# RS232Multiplexer.net
KiCad netlist of a schematic drawn in EAGLE
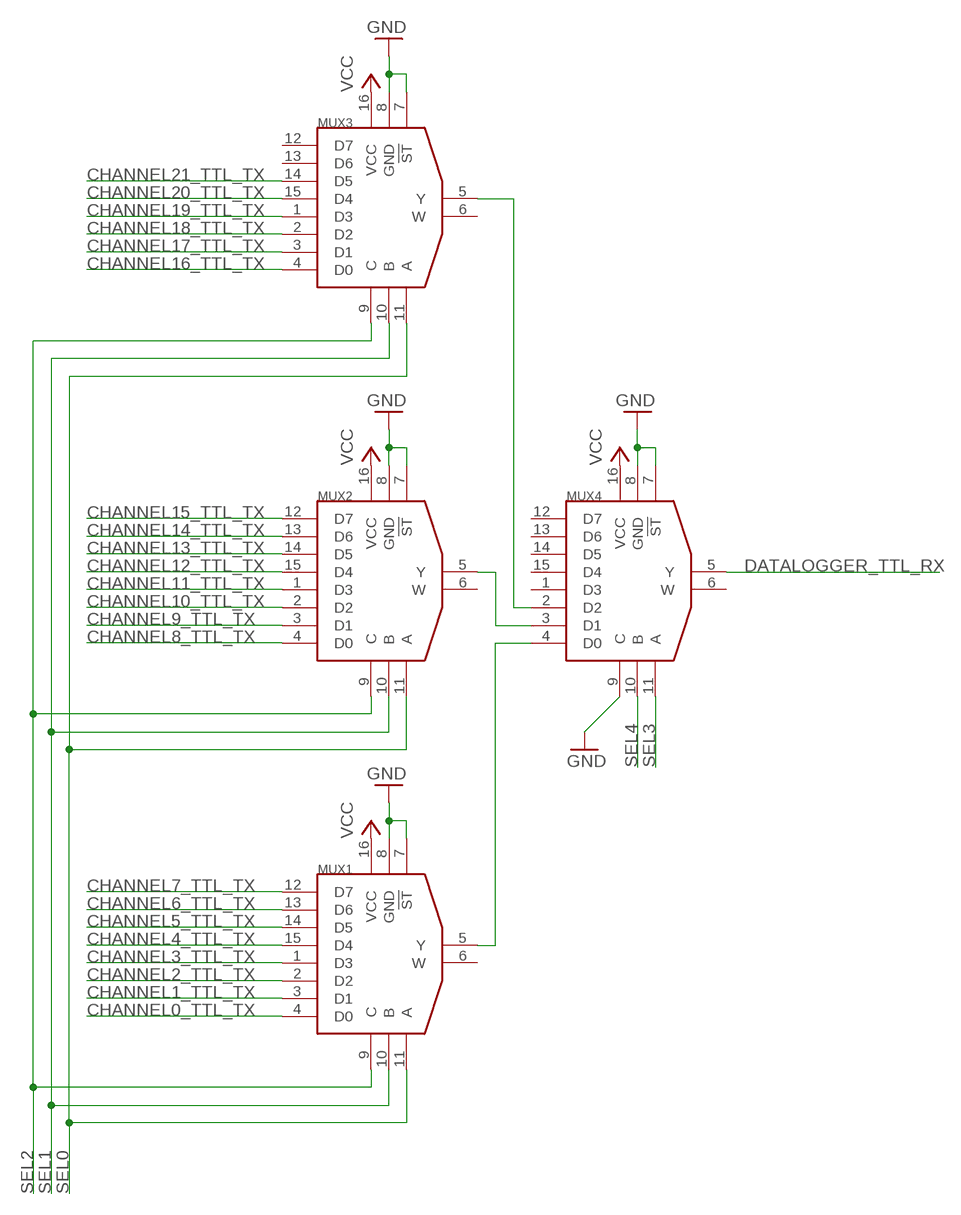
[diagram p0: schematic, sheet 1]
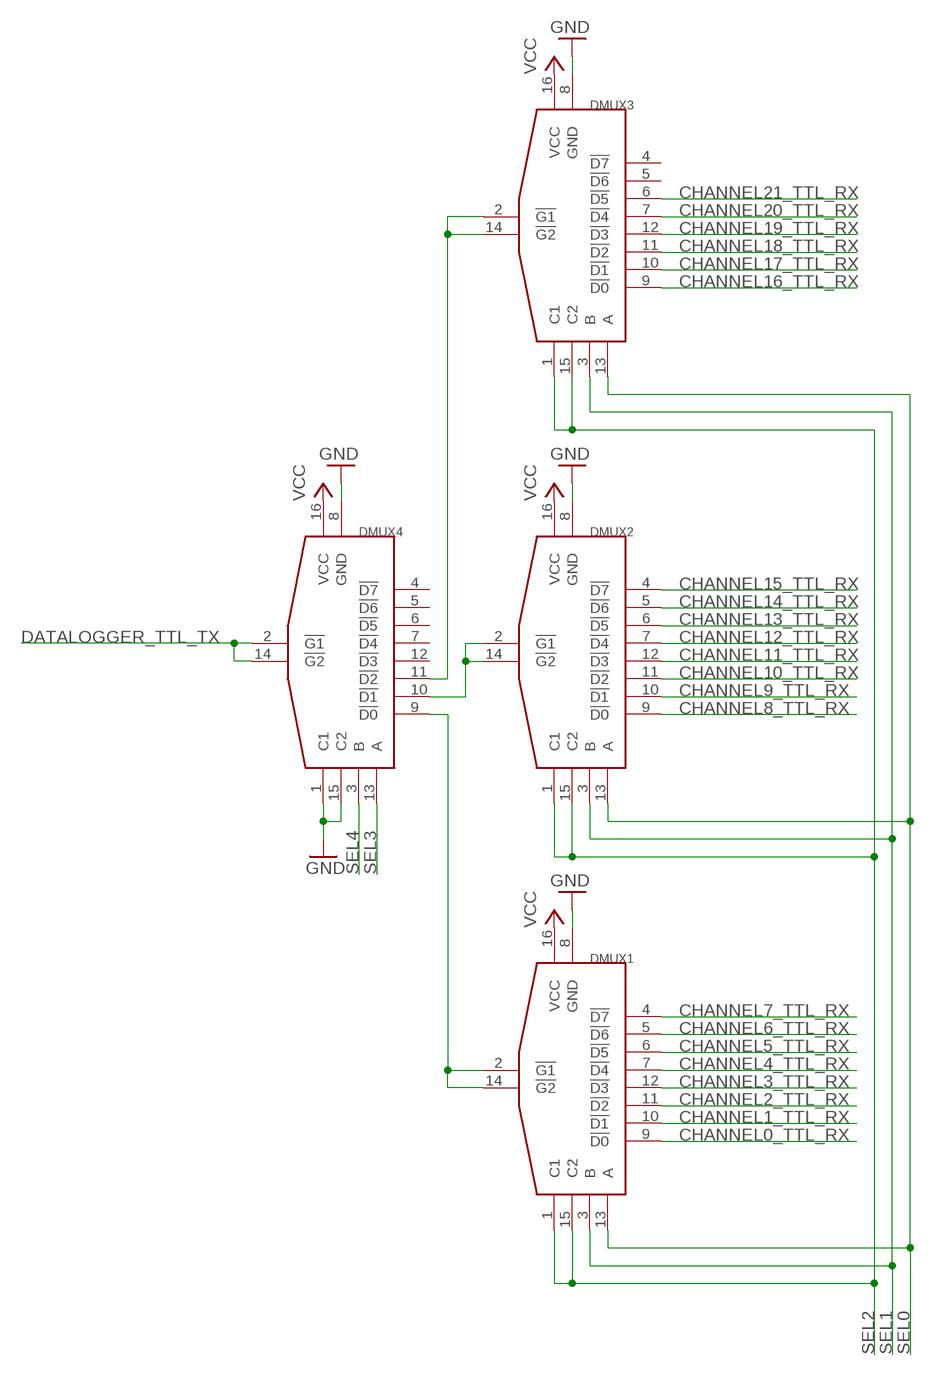
[diagram p1: schematic, sheet 2]
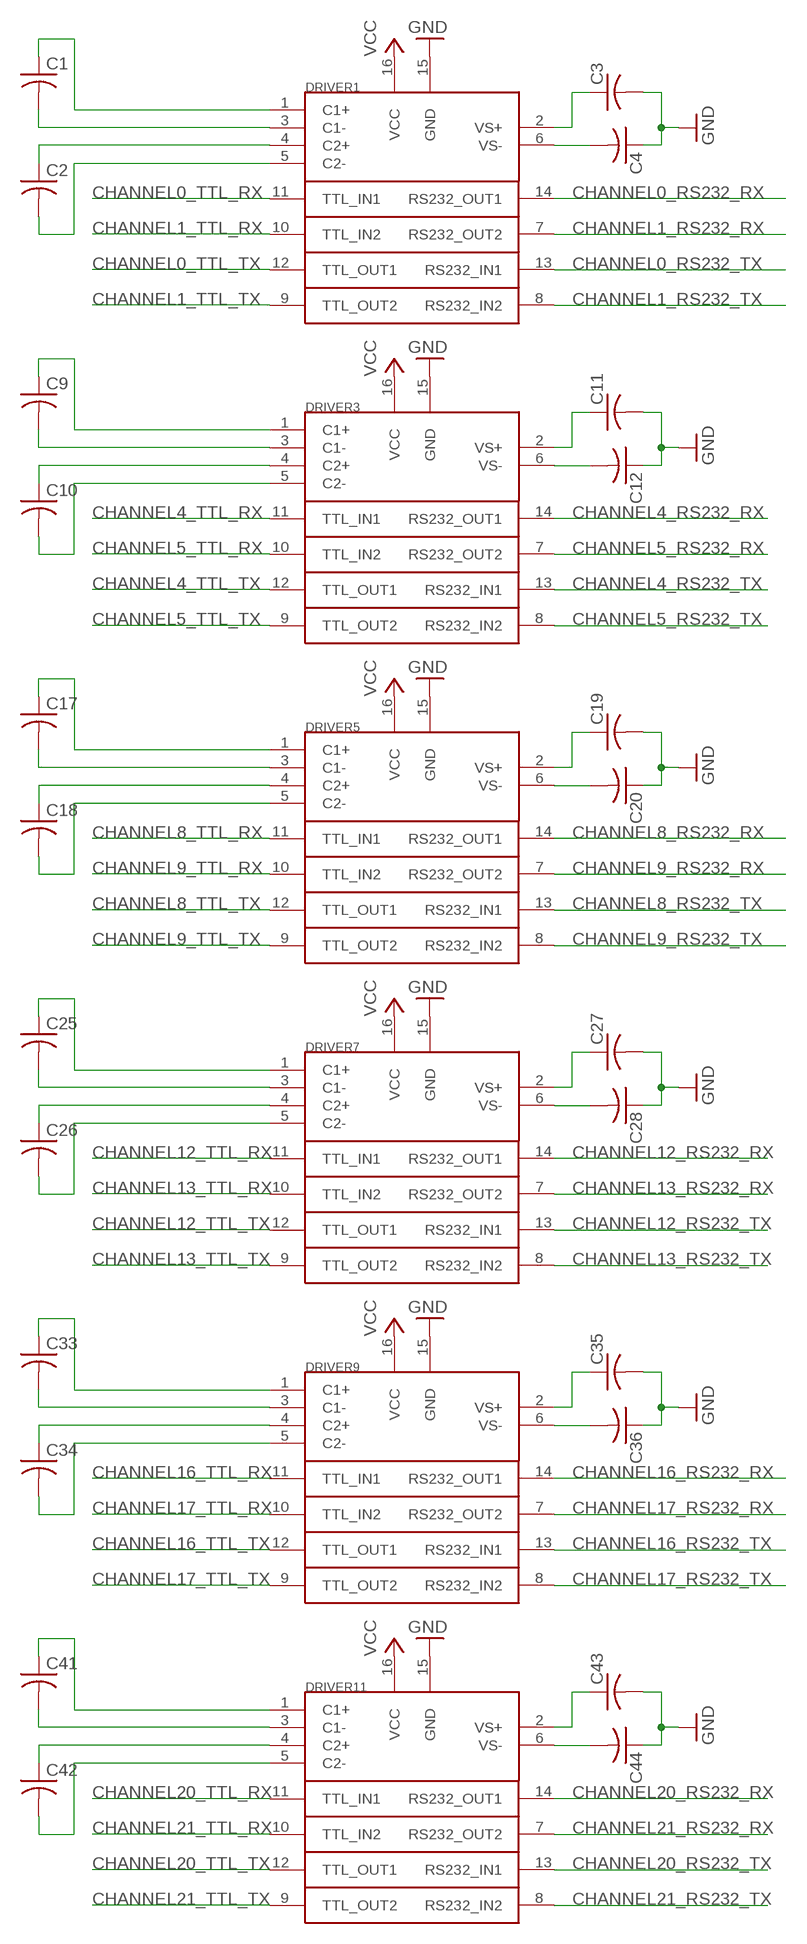
[diagram p2: schematic, sheet 3]
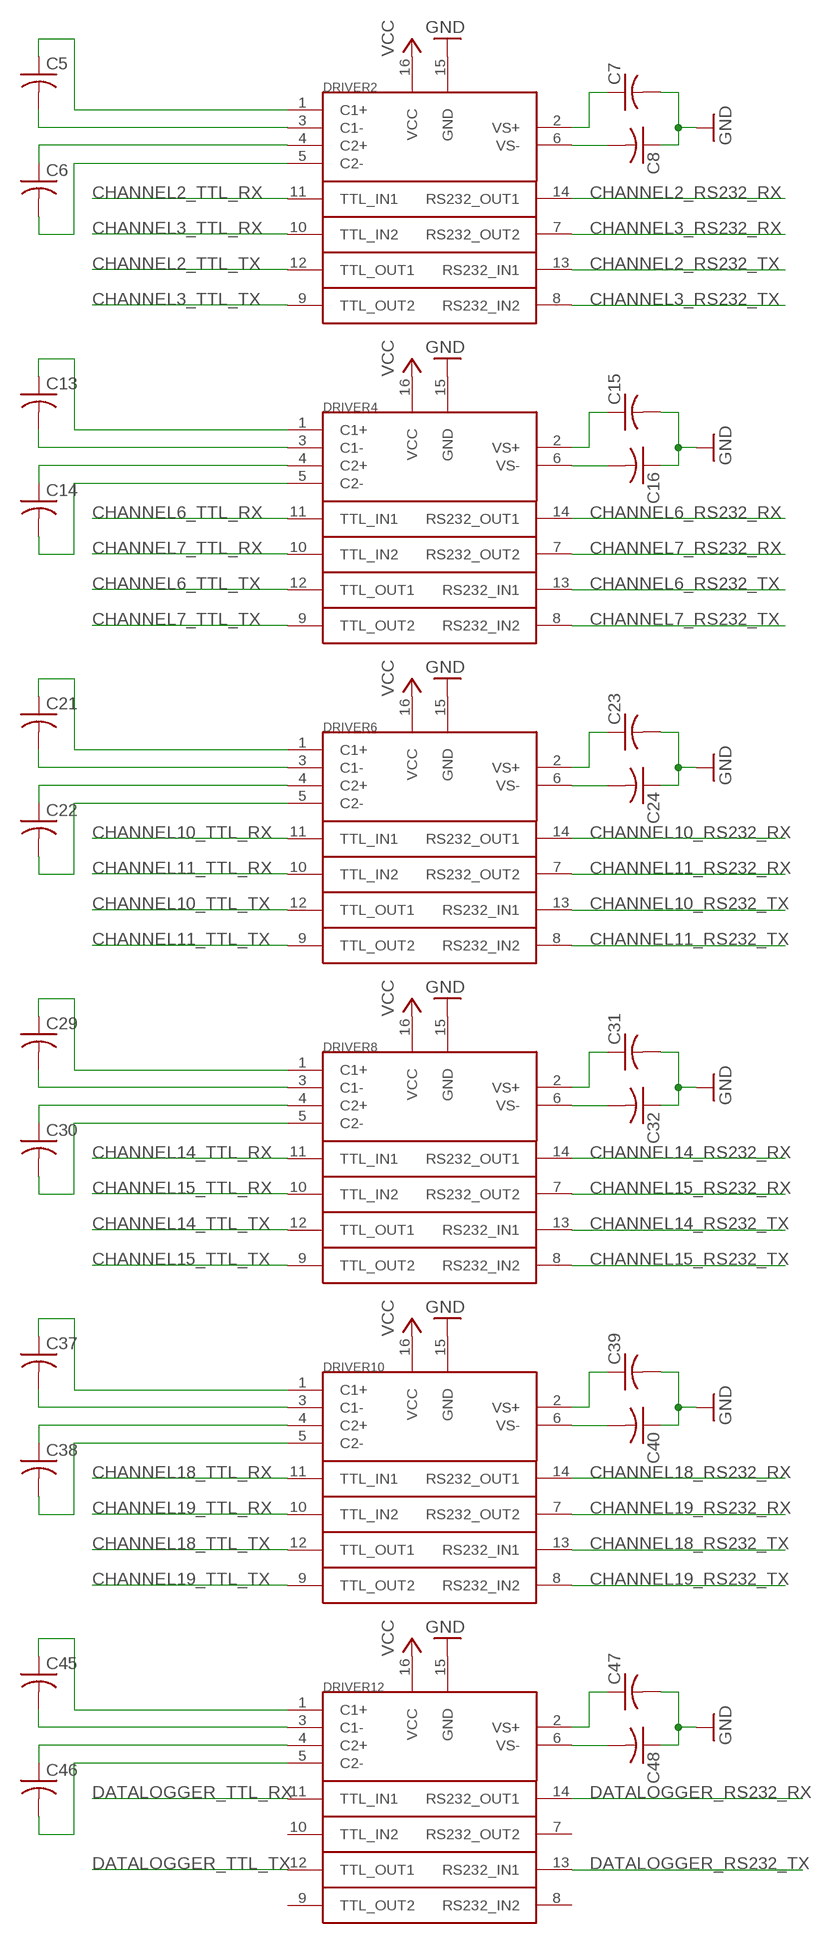
[diagram p3: schematic, sheet 4]

(export (version "E")
  (design (tool "Eeschema 10.0.6"))
  (components
    (comp (ref "C5")
      (value "C-US025-024X044")
      (footprint "eagle-import:C025-024X044")
      (libsource (lib "eagle-import") (part "C-US025-024X044"))
    )
    (comp (ref "C6")
      (value "C-US025-024X044")
      (footprint "eagle-import:C025-024X044")
      (libsource (lib "eagle-import") (part "C-US025-024X044"))
    )
    (comp (ref "C7")
      (value "C-US025-024X044")
      (footprint "eagle-import:C025-024X044")
      (libsource (lib "eagle-import") (part "C-US025-024X044"))
    )
    (comp (ref "C8")
      (value "C-US025-024X044")
      (footprint "eagle-import:C025-024X044")
      (libsource (lib "eagle-import") (part "C-US025-024X044"))
    )
    (comp (ref "C13")
      (value "C-US025-024X044")
      (footprint "eagle-import:C025-024X044")
      (libsource (lib "eagle-import") (part "C-US025-024X044"))
    )
    (comp (ref "C14")
      (value "C-US025-024X044")
      (footprint "eagle-import:C025-024X044")
      (libsource (lib "eagle-import") (part "C-US025-024X044"))
    )
    (comp (ref "C15")
      (value "C-US025-024X044")
      (footprint "eagle-import:C025-024X044")
      (libsource (lib "eagle-import") (part "C-US025-024X044"))
    )
    (comp (ref "C16")
      (value "C-US025-024X044")
      (footprint "eagle-import:C025-024X044")
      (libsource (lib "eagle-import") (part "C-US025-024X044"))
    )
    (comp (ref "C21")
      (value "C-US025-024X044")
      (footprint "eagle-import:C025-024X044")
      (libsource (lib "eagle-import") (part "C-US025-024X044"))
    )
    (comp (ref "C22")
      (value "C-US025-024X044")
      (footprint "eagle-import:C025-024X044")
      (libsource (lib "eagle-import") (part "C-US025-024X044"))
    )
    (comp (ref "C23")
      (value "C-US025-024X044")
      (footprint "eagle-import:C025-024X044")
      (libsource (lib "eagle-import") (part "C-US025-024X044"))
    )
    (comp (ref "C24")
      (value "C-US025-024X044")
      (footprint "eagle-import:C025-024X044")
      (libsource (lib "eagle-import") (part "C-US025-024X044"))
    )
    (comp (ref "C29")
      (value "C-US025-024X044")
      (footprint "eagle-import:C025-024X044")
      (libsource (lib "eagle-import") (part "C-US025-024X044"))
    )
    (comp (ref "C30")
      (value "C-US025-024X044")
      (footprint "eagle-import:C025-024X044")
      (libsource (lib "eagle-import") (part "C-US025-024X044"))
    )
    (comp (ref "C31")
      (value "C-US025-024X044")
      (footprint "eagle-import:C025-024X044")
      (libsource (lib "eagle-import") (part "C-US025-024X044"))
    )
    (comp (ref "C32")
      (value "C-US025-024X044")
      (footprint "eagle-import:C025-024X044")
      (libsource (lib "eagle-import") (part "C-US025-024X044"))
    )
    (comp (ref "C37")
      (value "C-US025-024X044")
      (footprint "eagle-import:C025-024X044")
      (libsource (lib "eagle-import") (part "C-US025-024X044"))
    )
    (comp (ref "C38")
      (value "C-US025-024X044")
      (footprint "eagle-import:C025-024X044")
      (libsource (lib "eagle-import") (part "C-US025-024X044"))
    )
    (comp (ref "C39")
      (value "C-US025-024X044")
      (footprint "eagle-import:C025-024X044")
      (libsource (lib "eagle-import") (part "C-US025-024X044"))
    )
    (comp (ref "C40")
      (value "C-US025-024X044")
      (footprint "eagle-import:C025-024X044")
      (libsource (lib "eagle-import") (part "C-US025-024X044"))
    )
    (comp (ref "C45")
      (value "C-US025-024X044")
      (footprint "eagle-import:C025-024X044")
      (libsource (lib "eagle-import") (part "C-US025-024X044"))
    )
    (comp (ref "C46")
      (value "C-US025-024X044")
      (footprint "eagle-import:C025-024X044")
      (libsource (lib "eagle-import") (part "C-US025-024X044"))
    )
    (comp (ref "C47")
      (value "C-US025-024X044")
      (footprint "eagle-import:C025-024X044")
      (libsource (lib "eagle-import") (part "C-US025-024X044"))
    )
    (comp (ref "C48")
      (value "C-US025-024X044")
      (footprint "eagle-import:C025-024X044")
      (libsource (lib "eagle-import") (part "C-US025-024X044"))
    )
    (comp (ref "DRIVER2")
      (value "MAX232_DUALEIA232DRIVER")
      (footprint "eagle-import:GENERIC16")
      (libsource (lib "eagle-import") (part "MAX232_DUALEIA232DRIVER"))
    )
    (comp (ref "DRIVER4")
      (value "MAX232_DUALEIA232DRIVER")
      (footprint "eagle-import:GENERIC16")
      (libsource (lib "eagle-import") (part "MAX232_DUALEIA232DRIVER"))
    )
    (comp (ref "DRIVER6")
      (value "MAX232_DUALEIA232DRIVER")
      (footprint "eagle-import:GENERIC16")
      (libsource (lib "eagle-import") (part "MAX232_DUALEIA232DRIVER"))
    )
    (comp (ref "DRIVER8")
      (value "MAX232_DUALEIA232DRIVER")
      (footprint "eagle-import:GENERIC16")
      (libsource (lib "eagle-import") (part "MAX232_DUALEIA232DRIVER"))
    )
    (comp (ref "DRIVER10")
      (value "MAX232_DUALEIA232DRIVER")
      (footprint "eagle-import:GENERIC16")
      (libsource (lib "eagle-import") (part "MAX232_DUALEIA232DRIVER"))
    )
    (comp (ref "DRIVER12")
      (value "MAX232_DUALEIA232DRIVER")
      (footprint "eagle-import:GENERIC16")
      (libsource (lib "eagle-import") (part "MAX232_DUALEIA232DRIVER"))
    )
    (comp (ref "C1")
      (value "C-US025-024X044")
      (footprint "eagle-import:C025-024X044")
      (libsource (lib "eagle-import") (part "C-US025-024X044"))
    )
    (comp (ref "C2")
      (value "C-US025-024X044")
      (footprint "eagle-import:C025-024X044")
      (libsource (lib "eagle-import") (part "C-US025-024X044"))
    )
    (comp (ref "C3")
      (value "C-US025-024X044")
      (footprint "eagle-import:C025-024X044")
      (libsource (lib "eagle-import") (part "C-US025-024X044"))
    )
    (comp (ref "C4")
      (value "C-US025-024X044")
      (footprint "eagle-import:C025-024X044")
      (libsource (lib "eagle-import") (part "C-US025-024X044"))
    )
    (comp (ref "C9")
      (value "C-US025-024X044")
      (footprint "eagle-import:C025-024X044")
      (libsource (lib "eagle-import") (part "C-US025-024X044"))
    )
    (comp (ref "C10")
      (value "C-US025-024X044")
      (footprint "eagle-import:C025-024X044")
      (libsource (lib "eagle-import") (part "C-US025-024X044"))
    )
    (comp (ref "C11")
      (value "C-US025-024X044")
      (footprint "eagle-import:C025-024X044")
      (libsource (lib "eagle-import") (part "C-US025-024X044"))
    )
    (comp (ref "C12")
      (value "C-US025-024X044")
      (footprint "eagle-import:C025-024X044")
      (libsource (lib "eagle-import") (part "C-US025-024X044"))
    )
    (comp (ref "C17")
      (value "C-US025-024X044")
      (footprint "eagle-import:C025-024X044")
      (libsource (lib "eagle-import") (part "C-US025-024X044"))
    )
    (comp (ref "C18")
      (value "C-US025-024X044")
      (footprint "eagle-import:C025-024X044")
      (libsource (lib "eagle-import") (part "C-US025-024X044"))
    )
    (comp (ref "C19")
      (value "C-US025-024X044")
      (footprint "eagle-import:C025-024X044")
      (libsource (lib "eagle-import") (part "C-US025-024X044"))
    )
    (comp (ref "C20")
      (value "C-US025-024X044")
      (footprint "eagle-import:C025-024X044")
      (libsource (lib "eagle-import") (part "C-US025-024X044"))
    )
    (comp (ref "C25")
      (value "C-US025-024X044")
      (footprint "eagle-import:C025-024X044")
      (libsource (lib "eagle-import") (part "C-US025-024X044"))
    )
    (comp (ref "C26")
      (value "C-US025-024X044")
      (footprint "eagle-import:C025-024X044")
      (libsource (lib "eagle-import") (part "C-US025-024X044"))
    )
    (comp (ref "C27")
      (value "C-US025-024X044")
      (footprint "eagle-import:C025-024X044")
      (libsource (lib "eagle-import") (part "C-US025-024X044"))
    )
    (comp (ref "C28")
      (value "C-US025-024X044")
      (footprint "eagle-import:C025-024X044")
      (libsource (lib "eagle-import") (part "C-US025-024X044"))
    )
    (comp (ref "C33")
      (value "C-US025-024X044")
      (footprint "eagle-import:C025-024X044")
      (libsource (lib "eagle-import") (part "C-US025-024X044"))
    )
    (comp (ref "C34")
      (value "C-US025-024X044")
      (footprint "eagle-import:C025-024X044")
      (libsource (lib "eagle-import") (part "C-US025-024X044"))
    )
    (comp (ref "C35")
      (value "C-US025-024X044")
      (footprint "eagle-import:C025-024X044")
      (libsource (lib "eagle-import") (part "C-US025-024X044"))
    )
    (comp (ref "C36")
      (value "C-US025-024X044")
      (footprint "eagle-import:C025-024X044")
      (libsource (lib "eagle-import") (part "C-US025-024X044"))
    )
    (comp (ref "C41")
      (value "C-US025-024X044")
      (footprint "eagle-import:C025-024X044")
      (libsource (lib "eagle-import") (part "C-US025-024X044"))
    )
    (comp (ref "C42")
      (value "C-US025-024X044")
      (footprint "eagle-import:C025-024X044")
      (libsource (lib "eagle-import") (part "C-US025-024X044"))
    )
    (comp (ref "C43")
      (value "C-US025-024X044")
      (footprint "eagle-import:C025-024X044")
      (libsource (lib "eagle-import") (part "C-US025-024X044"))
    )
    (comp (ref "C44")
      (value "C-US025-024X044")
      (footprint "eagle-import:C025-024X044")
      (libsource (lib "eagle-import") (part "C-US025-024X044"))
    )
    (comp (ref "DRIVER1")
      (value "MAX232_DUALEIA232DRIVER")
      (footprint "eagle-import:GENERIC16")
      (libsource (lib "eagle-import") (part "MAX232_DUALEIA232DRIVER"))
    )
    (comp (ref "DRIVER3")
      (value "MAX232_DUALEIA232DRIVER")
      (footprint "eagle-import:GENERIC16")
      (libsource (lib "eagle-import") (part "MAX232_DUALEIA232DRIVER"))
    )
    (comp (ref "DRIVER5")
      (value "MAX232_DUALEIA232DRIVER")
      (footprint "eagle-import:GENERIC16")
      (libsource (lib "eagle-import") (part "MAX232_DUALEIA232DRIVER"))
    )
    (comp (ref "DRIVER7")
      (value "MAX232_DUALEIA232DRIVER")
      (footprint "eagle-import:GENERIC16")
      (libsource (lib "eagle-import") (part "MAX232_DUALEIA232DRIVER"))
    )
    (comp (ref "DRIVER9")
      (value "MAX232_DUALEIA232DRIVER")
      (footprint "eagle-import:GENERIC16")
      (libsource (lib "eagle-import") (part "MAX232_DUALEIA232DRIVER"))
    )
    (comp (ref "DRIVER11")
      (value "MAX232_DUALEIA232DRIVER")
      (footprint "eagle-import:GENERIC16")
      (libsource (lib "eagle-import") (part "MAX232_DUALEIA232DRIVER"))
    )
    (comp (ref "DMUX1")
      (value "SN74LS156_DEMULTIPLEXER")
      (footprint "eagle-import:GENERIC16")
      (libsource (lib "eagle-import") (part "SN74LS156_DEMULTIPLEXER"))
    )
    (comp (ref "DMUX2")
      (value "SN74LS156_DEMULTIPLEXER")
      (footprint "eagle-import:GENERIC16")
      (libsource (lib "eagle-import") (part "SN74LS156_DEMULTIPLEXER"))
    )
    (comp (ref "DMUX3")
      (value "SN74LS156_DEMULTIPLEXER")
      (footprint "eagle-import:GENERIC16")
      (libsource (lib "eagle-import") (part "SN74LS156_DEMULTIPLEXER"))
    )
    (comp (ref "DMUX4")
      (value "SN74LS156_DEMULTIPLEXER")
      (footprint "eagle-import:GENERIC16")
      (libsource (lib "eagle-import") (part "SN74LS156_DEMULTIPLEXER"))
    )
    (comp (ref "MUX1")
      (value "M74HC251_MULTIPLEXER")
      (footprint "eagle-import:GENERIC16")
      (libsource (lib "eagle-import") (part "M74HC251_MULTIPLEXER"))
    )
    (comp (ref "MUX2")
      (value "M74HC251_MULTIPLEXER")
      (footprint "eagle-import:GENERIC16")
      (libsource (lib "eagle-import") (part "M74HC251_MULTIPLEXER"))
    )
    (comp (ref "MUX3")
      (value "M74HC251_MULTIPLEXER")
      (footprint "eagle-import:GENERIC16")
      (libsource (lib "eagle-import") (part "M74HC251_MULTIPLEXER"))
    )
    (comp (ref "MUX4")
      (value "M74HC251_MULTIPLEXER")
      (footprint "eagle-import:GENERIC16")
      (libsource (lib "eagle-import") (part "M74HC251_MULTIPLEXER"))
    )
  )
  (nets
    (net (code "1") (name "CHANNEL0_RS232_RX") (class "Default")
      (node (ref "DRIVER1") (pin "14") (pinfunction "RS232_OUT1_14") (pintype "bidirectional"))
    )
    (net (code "2") (name "CHANNEL0_RS232_TX") (class "Default")
      (node (ref "DRIVER1") (pin "13") (pinfunction "RS232_IN1_13") (pintype "bidirectional"))
    )
    (net (code "3") (name "CHANNEL0_TTL_RX") (class "Default")
      (node (ref "DMUX1") (pin "9") (pinfunction "~{D0}_9") (pintype "bidirectional"))
      (node (ref "DRIVER1") (pin "11") (pinfunction "TTL_IN1_11") (pintype "bidirectional"))
    )
    (net (code "4") (name "CHANNEL0_TTL_TX") (class "Default")
      (node (ref "DRIVER1") (pin "12") (pinfunction "TTL_OUT1_12") (pintype "bidirectional"))
      (node (ref "MUX1") (pin "4") (pinfunction "D0_4") (pintype "bidirectional"))
    )
    (net (code "5") (name "CHANNEL1_RS232_RX") (class "Default")
      (node (ref "DRIVER1") (pin "7") (pinfunction "RS232_OUT2_7") (pintype "bidirectional"))
    )
    (net (code "6") (name "CHANNEL1_RS232_TX") (class "Default")
      (node (ref "DRIVER1") (pin "8") (pinfunction "RS232_IN2_8") (pintype "bidirectional"))
    )
    (net (code "7") (name "CHANNEL1_TTL_RX") (class "Default")
      (node (ref "DMUX1") (pin "10") (pinfunction "~{D1}_10") (pintype "bidirectional"))
      (node (ref "DRIVER1") (pin "10") (pinfunction "TTL_IN2_10") (pintype "bidirectional"))
    )
    (net (code "8") (name "CHANNEL1_TTL_TX") (class "Default")
      (node (ref "DRIVER1") (pin "9") (pinfunction "TTL_OUT2_9") (pintype "bidirectional"))
      (node (ref "MUX1") (pin "3") (pinfunction "D1_3") (pintype "bidirectional"))
    )
    (net (code "9") (name "CHANNEL2_RS232_RX") (class "Default")
      (node (ref "DRIVER2") (pin "14") (pinfunction "RS232_OUT1_14") (pintype "bidirectional"))
    )
    (net (code "10") (name "CHANNEL2_RS232_TX") (class "Default")
      (node (ref "DRIVER2") (pin "13") (pinfunction "RS232_IN1_13") (pintype "bidirectional"))
    )
    (net (code "11") (name "CHANNEL2_TTL_RX") (class "Default")
      (node (ref "DMUX1") (pin "11") (pinfunction "~{D2}_11") (pintype "bidirectional"))
      (node (ref "DRIVER2") (pin "11") (pinfunction "TTL_IN1_11") (pintype "bidirectional"))
    )
    (net (code "12") (name "CHANNEL2_TTL_TX") (class "Default")
      (node (ref "DRIVER2") (pin "12") (pinfunction "TTL_OUT1_12") (pintype "bidirectional"))
      (node (ref "MUX1") (pin "2") (pinfunction "D2_2") (pintype "bidirectional"))
    )
    (net (code "13") (name "CHANNEL3_RS232_RX") (class "Default")
      (node (ref "DRIVER2") (pin "7") (pinfunction "RS232_OUT2_7") (pintype "bidirectional"))
    )
    (net (code "14") (name "CHANNEL3_RS232_TX") (class "Default")
      (node (ref "DRIVER2") (pin "8") (pinfunction "RS232_IN2_8") (pintype "bidirectional"))
    )
    (net (code "15") (name "CHANNEL3_TTL_RX") (class "Default")
      (node (ref "DMUX1") (pin "12") (pinfunction "~{D3}_12") (pintype "bidirectional"))
      (node (ref "DRIVER2") (pin "10") (pinfunction "TTL_IN2_10") (pintype "bidirectional"))
    )
    (net (code "16") (name "CHANNEL3_TTL_TX") (class "Default")
      (node (ref "DRIVER2") (pin "9") (pinfunction "TTL_OUT2_9") (pintype "bidirectional"))
      (node (ref "MUX1") (pin "1") (pinfunction "D3_1") (pintype "bidirectional"))
    )
    (net (code "17") (name "CHANNEL4_RS232_RX") (class "Default")
      (node (ref "DRIVER3") (pin "14") (pinfunction "RS232_OUT1_14") (pintype "bidirectional"))
    )
    (net (code "18") (name "CHANNEL4_RS232_TX") (class "Default")
      (node (ref "DRIVER3") (pin "13") (pinfunction "RS232_IN1_13") (pintype "bidirectional"))
    )
    (net (code "19") (name "CHANNEL4_TTL_RX") (class "Default")
      (node (ref "DMUX1") (pin "7") (pinfunction "~{D4}_7") (pintype "bidirectional"))
      (node (ref "DRIVER3") (pin "11") (pinfunction "TTL_IN1_11") (pintype "bidirectional"))
    )
    (net (code "20") (name "CHANNEL4_TTL_TX") (class "Default")
      (node (ref "DRIVER3") (pin "12") (pinfunction "TTL_OUT1_12") (pintype "bidirectional"))
      (node (ref "MUX1") (pin "15") (pinfunction "D4_15") (pintype "bidirectional"))
    )
    (net (code "21") (name "CHANNEL5_RS232_RX") (class "Default")
      (node (ref "DRIVER3") (pin "7") (pinfunction "RS232_OUT2_7") (pintype "bidirectional"))
    )
    (net (code "22") (name "CHANNEL5_RS232_TX") (class "Default")
      (node (ref "DRIVER3") (pin "8") (pinfunction "RS232_IN2_8") (pintype "bidirectional"))
    )
    (net (code "23") (name "CHANNEL5_TTL_RX") (class "Default")
      (node (ref "DMUX1") (pin "6") (pinfunction "~{D5}_6") (pintype "bidirectional"))
      (node (ref "DRIVER3") (pin "10") (pinfunction "TTL_IN2_10") (pintype "bidirectional"))
    )
    (net (code "24") (name "CHANNEL5_TTL_TX") (class "Default")
      (node (ref "DRIVER3") (pin "9") (pinfunction "TTL_OUT2_9") (pintype "bidirectional"))
      (node (ref "MUX1") (pin "14") (pinfunction "D5_14") (pintype "bidirectional"))
    )
    (net (code "25") (name "CHANNEL6_RS232_RX") (class "Default")
      (node (ref "DRIVER4") (pin "14") (pinfunction "RS232_OUT1_14") (pintype "bidirectional"))
    )
    (net (code "26") (name "CHANNEL6_RS232_TX") (class "Default")
      (node (ref "DRIVER4") (pin "13") (pinfunction "RS232_IN1_13") (pintype "bidirectional"))
    )
    (net (code "27") (name "CHANNEL6_TTL_RX") (class "Default")
      (node (ref "DMUX1") (pin "5") (pinfunction "~{D6}_5") (pintype "bidirectional"))
      (node (ref "DRIVER4") (pin "11") (pinfunction "TTL_IN1_11") (pintype "bidirectional"))
    )
    (net (code "28") (name "CHANNEL6_TTL_TX") (class "Default")
      (node (ref "DRIVER4") (pin "12") (pinfunction "TTL_OUT1_12") (pintype "bidirectional"))
      (node (ref "MUX1") (pin "13") (pinfunction "D6_13") (pintype "bidirectional"))
    )
    (net (code "29") (name "CHANNEL7_RS232_RX") (class "Default")
      (node (ref "DRIVER4") (pin "7") (pinfunction "RS232_OUT2_7") (pintype "bidirectional"))
    )
    (net (code "30") (name "CHANNEL7_RS232_TX") (class "Default")
      (node (ref "DRIVER4") (pin "8") (pinfunction "RS232_IN2_8") (pintype "bidirectional"))
    )
    (net (code "31") (name "CHANNEL7_TTL_RX") (class "Default")
      (node (ref "DMUX1") (pin "4") (pinfunction "~{D7}_4") (pintype "bidirectional"))
      (node (ref "DRIVER4") (pin "10") (pinfunction "TTL_IN2_10") (pintype "bidirectional"))
    )
    (net (code "32") (name "CHANNEL7_TTL_TX") (class "Default")
      (node (ref "DRIVER4") (pin "9") (pinfunction "TTL_OUT2_9") (pintype "bidirectional"))
      (node (ref "MUX1") (pin "12") (pinfunction "D7_12") (pintype "bidirectional"))
    )
    (net (code "33") (name "CHANNEL8_RS232_RX") (class "Default")
      (node (ref "DRIVER5") (pin "14") (pinfunction "RS232_OUT1_14") (pintype "bidirectional"))
    )
    (net (code "34") (name "CHANNEL8_RS232_TX") (class "Default")
      (node (ref "DRIVER5") (pin "13") (pinfunction "RS232_IN1_13") (pintype "bidirectional"))
    )
    (net (code "35") (name "CHANNEL8_TTL_RX") (class "Default")
      (node (ref "DMUX2") (pin "9") (pinfunction "~{D0}_9") (pintype "bidirectional"))
      (node (ref "DRIVER5") (pin "11") (pinfunction "TTL_IN1_11") (pintype "bidirectional"))
    )
    (net (code "36") (name "CHANNEL8_TTL_TX") (class "Default")
      (node (ref "DRIVER5") (pin "12") (pinfunction "TTL_OUT1_12") (pintype "bidirectional"))
      (node (ref "MUX2") (pin "4") (pinfunction "D0_4") (pintype "bidirectional"))
    )
    (net (code "37") (name "CHANNEL9_RS232_RX") (class "Default")
      (node (ref "DRIVER5") (pin "7") (pinfunction "RS232_OUT2_7") (pintype "bidirectional"))
    )
    (net (code "38") (name "CHANNEL9_RS232_TX") (class "Default")
      (node (ref "DRIVER5") (pin "8") (pinfunction "RS232_IN2_8") (pintype "bidirectional"))
    )
    (net (code "39") (name "CHANNEL9_TTL_RX") (class "Default")
      (node (ref "DMUX2") (pin "10") (pinfunction "~{D1}_10") (pintype "bidirectional"))
      (node (ref "DRIVER5") (pin "10") (pinfunction "TTL_IN2_10") (pintype "bidirectional"))
    )
    (net (code "40") (name "CHANNEL9_TTL_TX") (class "Default")
      (node (ref "DRIVER5") (pin "9") (pinfunction "TTL_OUT2_9") (pintype "bidirectional"))
      (node (ref "MUX2") (pin "3") (pinfunction "D1_3") (pintype "bidirectional"))
    )
    (net (code "41") (name "CHANNEL10_RS232_RX") (class "Default")
      (node (ref "DRIVER6") (pin "14") (pinfunction "RS232_OUT1_14") (pintype "bidirectional"))
    )
    (net (code "42") (name "CHANNEL10_RS232_TX") (class "Default")
      (node (ref "DRIVER6") (pin "13") (pinfunction "RS232_IN1_13") (pintype "bidirectional"))
    )
    (net (code "43") (name "CHANNEL10_TTL_RX") (class "Default")
      (node (ref "DMUX2") (pin "11") (pinfunction "~{D2}_11") (pintype "bidirectional"))
      (node (ref "DRIVER6") (pin "11") (pinfunction "TTL_IN1_11") (pintype "bidirectional"))
    )
    (net (code "44") (name "CHANNEL10_TTL_TX") (class "Default")
      (node (ref "DRIVER6") (pin "12") (pinfunction "TTL_OUT1_12") (pintype "bidirectional"))
      (node (ref "MUX2") (pin "2") (pinfunction "D2_2") (pintype "bidirectional"))
    )
    (net (code "45") (name "CHANNEL11_RS232_RX") (class "Default")
      (node (ref "DRIVER6") (pin "7") (pinfunction "RS232_OUT2_7") (pintype "bidirectional"))
    )
    (net (code "46") (name "CHANNEL11_RS232_TX") (class "Default")
      (node (ref "DRIVER6") (pin "8") (pinfunction "RS232_IN2_8") (pintype "bidirectional"))
    )
    (net (code "47") (name "CHANNEL11_TTL_RX") (class "Default")
      (node (ref "DMUX2") (pin "12") (pinfunction "~{D3}_12") (pintype "bidirectional"))
      (node (ref "DRIVER6") (pin "10") (pinfunction "TTL_IN2_10") (pintype "bidirectional"))
    )
    (net (code "48") (name "CHANNEL11_TTL_TX") (class "Default")
      (node (ref "DRIVER6") (pin "9") (pinfunction "TTL_OUT2_9") (pintype "bidirectional"))
      (node (ref "MUX2") (pin "1") (pinfunction "D3_1") (pintype "bidirectional"))
    )
    (net (code "49") (name "CHANNEL12_RS232_RX") (class "Default")
      (node (ref "DRIVER7") (pin "14") (pinfunction "RS232_OUT1_14") (pintype "bidirectional"))
    )
    (net (code "50") (name "CHANNEL12_RS232_TX") (class "Default")
      (node (ref "DRIVER7") (pin "13") (pinfunction "RS232_IN1_13") (pintype "bidirectional"))
    )
    (net (code "51") (name "CHANNEL12_TTL_RX") (class "Default")
      (node (ref "DMUX2") (pin "7") (pinfunction "~{D4}_7") (pintype "bidirectional"))
      (node (ref "DRIVER7") (pin "11") (pinfunction "TTL_IN1_11") (pintype "bidirectional"))
    )
    (net (code "52") (name "CHANNEL12_TTL_TX") (class "Default")
      (node (ref "DRIVER7") (pin "12") (pinfunction "TTL_OUT1_12") (pintype "bidirectional"))
      (node (ref "MUX2") (pin "15") (pinfunction "D4_15") (pintype "bidirectional"))
    )
    (net (code "53") (name "CHANNEL13_RS232_RX") (class "Default")
      (node (ref "DRIVER7") (pin "7") (pinfunction "RS232_OUT2_7") (pintype "bidirectional"))
    )
    (net (code "54") (name "CHANNEL13_RS232_TX") (class "Default")
      (node (ref "DRIVER7") (pin "8") (pinfunction "RS232_IN2_8") (pintype "bidirectional"))
    )
    (net (code "55") (name "CHANNEL13_TTL_RX") (class "Default")
      (node (ref "DMUX2") (pin "6") (pinfunction "~{D5}_6") (pintype "bidirectional"))
      (node (ref "DRIVER7") (pin "10") (pinfunction "TTL_IN2_10") (pintype "bidirectional"))
    )
    (net (code "56") (name "CHANNEL13_TTL_TX") (class "Default")
      (node (ref "DRIVER7") (pin "9") (pinfunction "TTL_OUT2_9") (pintype "bidirectional"))
      (node (ref "MUX2") (pin "14") (pinfunction "D5_14") (pintype "bidirectional"))
    )
    (net (code "57") (name "CHANNEL14_RS232_RX") (class "Default")
      (node (ref "DRIVER8") (pin "14") (pinfunction "RS232_OUT1_14") (pintype "bidirectional"))
    )
    (net (code "58") (name "CHANNEL14_RS232_TX") (class "Default")
      (node (ref "DRIVER8") (pin "13") (pinfunction "RS232_IN1_13") (pintype "bidirectional"))
    )
    (net (code "59") (name "CHANNEL14_TTL_RX") (class "Default")
      (node (ref "DMUX2") (pin "5") (pinfunction "~{D6}_5") (pintype "bidirectional"))
      (node (ref "DRIVER8") (pin "11") (pinfunction "TTL_IN1_11") (pintype "bidirectional"))
    )
    (net (code "60") (name "CHANNEL14_TTL_TX") (class "Default")
      (node (ref "DRIVER8") (pin "12") (pinfunction "TTL_OUT1_12") (pintype "bidirectional"))
      (node (ref "MUX2") (pin "13") (pinfunction "D6_13") (pintype "bidirectional"))
    )
    (net (code "61") (name "CHANNEL15_RS232_RX") (class "Default")
      (node (ref "DRIVER8") (pin "7") (pinfunction "RS232_OUT2_7") (pintype "bidirectional"))
    )
    (net (code "62") (name "CHANNEL15_RS232_TX") (class "Default")
      (node (ref "DRIVER8") (pin "8") (pinfunction "RS232_IN2_8") (pintype "bidirectional"))
    )
    (net (code "63") (name "CHANNEL15_TTL_RX") (class "Default")
      (node (ref "DMUX2") (pin "4") (pinfunction "~{D7}_4") (pintype "bidirectional"))
      (node (ref "DRIVER8") (pin "10") (pinfunction "TTL_IN2_10") (pintype "bidirectional"))
    )
    (net (code "64") (name "CHANNEL15_TTL_TX") (class "Default")
      (node (ref "DRIVER8") (pin "9") (pinfunction "TTL_OUT2_9") (pintype "bidirectional"))
      (node (ref "MUX2") (pin "12") (pinfunction "D7_12") (pintype "bidirectional"))
    )
    (net (code "65") (name "CHANNEL16_RS232_RX") (class "Default")
      (node (ref "DRIVER9") (pin "14") (pinfunction "RS232_OUT1_14") (pintype "bidirectional"))
    )
    (net (code "66") (name "CHANNEL16_RS232_TX") (class "Default")
      (node (ref "DRIVER9") (pin "13") (pinfunction "RS232_IN1_13") (pintype "bidirectional"))
    )
    (net (code "67") (name "CHANNEL16_TTL_RX") (class "Default")
      (node (ref "DMUX3") (pin "9") (pinfunction "~{D0}_9") (pintype "bidirectional"))
      (node (ref "DRIVER9") (pin "11") (pinfunction "TTL_IN1_11") (pintype "bidirectional"))
    )
    (net (code "68") (name "CHANNEL16_TTL_TX") (class "Default")
      (node (ref "DRIVER9") (pin "12") (pinfunction "TTL_OUT1_12") (pintype "bidirectional"))
      (node (ref "MUX3") (pin "4") (pinfunction "D0_4") (pintype "bidirectional"))
    )
    (net (code "69") (name "CHANNEL17_RS232_RX") (class "Default")
      (node (ref "DRIVER9") (pin "7") (pinfunction "RS232_OUT2_7") (pintype "bidirectional"))
    )
    (net (code "70") (name "CHANNEL17_RS232_TX") (class "Default")
      (node (ref "DRIVER9") (pin "8") (pinfunction "RS232_IN2_8") (pintype "bidirectional"))
    )
    (net (code "71") (name "CHANNEL17_TTL_RX") (class "Default")
      (node (ref "DMUX3") (pin "10") (pinfunction "~{D1}_10") (pintype "bidirectional"))
      (node (ref "DRIVER9") (pin "10") (pinfunction "TTL_IN2_10") (pintype "bidirectional"))
    )
    (net (code "72") (name "CHANNEL17_TTL_TX") (class "Default")
      (node (ref "DRIVER9") (pin "9") (pinfunction "TTL_OUT2_9") (pintype "bidirectional"))
      (node (ref "MUX3") (pin "3") (pinfunction "D1_3") (pintype "bidirectional"))
    )
    (net (code "73") (name "CHANNEL18_RS232_RX") (class "Default")
      (node (ref "DRIVER10") (pin "14") (pinfunction "RS232_OUT1_14") (pintype "bidirectional"))
    )
    (net (code "74") (name "CHANNEL18_RS232_TX") (class "Default")
      (node (ref "DRIVER10") (pin "13") (pinfunction "RS232_IN1_13") (pintype "bidirectional"))
    )
    (net (code "75") (name "CHANNEL18_TTL_RX") (class "Default")
      (node (ref "DMUX3") (pin "11") (pinfunction "~{D2}_11") (pintype "bidirectional"))
      (node (ref "DRIVER10") (pin "11") (pinfunction "TTL_IN1_11") (pintype "bidirectional"))
    )
    (net (code "76") (name "CHANNEL18_TTL_TX") (class "Default")
      (node (ref "DRIVER10") (pin "12") (pinfunction "TTL_OUT1_12") (pintype "bidirectional"))
      (node (ref "MUX3") (pin "2") (pinfunction "D2_2") (pintype "bidirectional"))
    )
    (net (code "77") (name "CHANNEL19_RS232_RX") (class "Default")
      (node (ref "DRIVER10") (pin "7") (pinfunction "RS232_OUT2_7") (pintype "bidirectional"))
    )
    (net (code "78") (name "CHANNEL19_RS232_TX") (class "Default")
      (node (ref "DRIVER10") (pin "8") (pinfunction "RS232_IN2_8") (pintype "bidirectional"))
    )
    (net (code "79") (name "CHANNEL19_TTL_RX") (class "Default")
      (node (ref "DMUX3") (pin "12") (pinfunction "~{D3}_12") (pintype "bidirectional"))
      (node (ref "DRIVER10") (pin "10") (pinfunction "TTL_IN2_10") (pintype "bidirectional"))
    )
    (net (code "80") (name "CHANNEL19_TTL_TX") (class "Default")
      (node (ref "DRIVER10") (pin "9") (pinfunction "TTL_OUT2_9") (pintype "bidirectional"))
      (node (ref "MUX3") (pin "1") (pinfunction "D3_1") (pintype "bidirectional"))
    )
    (net (code "81") (name "CHANNEL20_RS232_RX") (class "Default")
      (node (ref "DRIVER11") (pin "14") (pinfunction "RS232_OUT1_14") (pintype "bidirectional"))
    )
    (net (code "82") (name "CHANNEL20_RS232_TX") (class "Default")
      (node (ref "DRIVER11") (pin "13") (pinfunction "RS232_IN1_13") (pintype "bidirectional"))
    )
    (net (code "83") (name "CHANNEL20_TTL_RX") (class "Default")
      (node (ref "DMUX3") (pin "7") (pinfunction "~{D4}_7") (pintype "bidirectional"))
      (node (ref "DRIVER11") (pin "11") (pinfunction "TTL_IN1_11") (pintype "bidirectional"))
    )
    (net (code "84") (name "CHANNEL20_TTL_TX") (class "Default")
      (node (ref "DRIVER11") (pin "12") (pinfunction "TTL_OUT1_12") (pintype "bidirectional"))
      (node (ref "MUX3") (pin "15") (pinfunction "D4_15") (pintype "bidirectional"))
    )
    (net (code "85") (name "CHANNEL21_RS232_RX") (class "Default")
      (node (ref "DRIVER11") (pin "7") (pinfunction "RS232_OUT2_7") (pintype "bidirectional"))
    )
    (net (code "86") (name "CHANNEL21_RS232_TX") (class "Default")
      (node (ref "DRIVER11") (pin "8") (pinfunction "RS232_IN2_8") (pintype "bidirectional"))
    )
    (net (code "87") (name "CHANNEL21_TTL_RX") (class "Default")
      (node (ref "DMUX3") (pin "6") (pinfunction "~{D5}_6") (pintype "bidirectional"))
      (node (ref "DRIVER11") (pin "10") (pinfunction "TTL_IN2_10") (pintype "bidirectional"))
    )
    (net (code "88") (name "CHANNEL21_TTL_TX") (class "Default")
      (node (ref "DRIVER11") (pin "9") (pinfunction "TTL_OUT2_9") (pintype "bidirectional"))
      (node (ref "MUX3") (pin "14") (pinfunction "D5_14") (pintype "bidirectional"))
    )
    (net (code "89") (name "DATALOGGER_RS232_RX") (class "Default")
      (node (ref "DRIVER12") (pin "14") (pinfunction "RS232_OUT1_14") (pintype "bidirectional"))
    )
    (net (code "90") (name "DATALOGGER_RS232_TX") (class "Default")
      (node (ref "DRIVER12") (pin "13") (pinfunction "RS232_IN1_13") (pintype "bidirectional"))
    )
    (net (code "91") (name "DATALOGGER_TTL_RX") (class "Default")
      (node (ref "DRIVER12") (pin "11") (pinfunction "TTL_IN1_11") (pintype "bidirectional"))
      (node (ref "MUX4") (pin "5") (pinfunction "Y_5") (pintype "bidirectional"))
    )
    (net (code "92") (name "DATALOGGER_TTL_TX") (class "Default")
      (node (ref "DMUX4") (pin "14") (pinfunction "~{G2}_14") (pintype "bidirectional"))
      (node (ref "DMUX4") (pin "2") (pinfunction "~{G1}_2") (pintype "bidirectional"))
      (node (ref "DRIVER12") (pin "12") (pinfunction "TTL_OUT1_12") (pintype "bidirectional"))
    )
    (net (code "93") (name "GND") (class "Default")
      (node (ref "C11") (pin "2") (pinfunction "2_2") (pintype "passive"))
      (node (ref "C12") (pin "1") (pinfunction "1_1") (pintype "passive"))
      (node (ref "C15") (pin "2") (pinfunction "2_2") (pintype "passive"))
      (node (ref "C16") (pin "1") (pinfunction "1_1") (pintype "passive"))
      (node (ref "C19") (pin "2") (pinfunction "2_2") (pintype "passive"))
      (node (ref "C20") (pin "1") (pinfunction "1_1") (pintype "passive"))
      (node (ref "C23") (pin "2") (pinfunction "2_2") (pintype "passive"))
      (node (ref "C24") (pin "1") (pinfunction "1_1") (pintype "passive"))
      (node (ref "C27") (pin "2") (pinfunction "2_2") (pintype "passive"))
      (node (ref "C28") (pin "1") (pinfunction "1_1") (pintype "passive"))
      (node (ref "C3") (pin "2") (pinfunction "2_2") (pintype "passive"))
      (node (ref "C31") (pin "2") (pinfunction "2_2") (pintype "passive"))
      (node (ref "C32") (pin "1") (pinfunction "1_1") (pintype "passive"))
      (node (ref "C35") (pin "2") (pinfunction "2_2") (pintype "passive"))
      (node (ref "C36") (pin "1") (pinfunction "1_1") (pintype "passive"))
      (node (ref "C39") (pin "2") (pinfunction "2_2") (pintype "passive"))
      (node (ref "C4") (pin "1") (pinfunction "1_1") (pintype "passive"))
      (node (ref "C40") (pin "1") (pinfunction "1_1") (pintype "passive"))
      (node (ref "C43") (pin "2") (pinfunction "2_2") (pintype "passive"))
      (node (ref "C44") (pin "1") (pinfunction "1_1") (pintype "passive"))
      (node (ref "C47") (pin "2") (pinfunction "2_2") (pintype "passive"))
      (node (ref "C48") (pin "1") (pinfunction "1_1") (pintype "passive"))
      (node (ref "C7") (pin "2") (pinfunction "2_2") (pintype "passive"))
      (node (ref "C8") (pin "1") (pinfunction "1_1") (pintype "passive"))
      (node (ref "DMUX1") (pin "8") (pinfunction "GND_8") (pintype "bidirectional"))
      (node (ref "DMUX2") (pin "8") (pinfunction "GND_8") (pintype "bidirectional"))
      (node (ref "DMUX3") (pin "8") (pinfunction "GND_8") (pintype "bidirectional"))
      (node (ref "DMUX4") (pin "1") (pinfunction "C1_1") (pintype "bidirectional"))
      (node (ref "DMUX4") (pin "15") (pinfunction "C2_15") (pintype "bidirectional"))
      (node (ref "DMUX4") (pin "8") (pinfunction "GND_8") (pintype "bidirectional"))
      (node (ref "DRIVER1") (pin "15") (pinfunction "GND_15") (pintype "bidirectional"))
      (node (ref "DRIVER10") (pin "15") (pinfunction "GND_15") (pintype "bidirectional"))
      (node (ref "DRIVER11") (pin "15") (pinfunction "GND_15") (pintype "bidirectional"))
      (node (ref "DRIVER12") (pin "15") (pinfunction "GND_15") (pintype "bidirectional"))
      (node (ref "DRIVER2") (pin "15") (pinfunction "GND_15") (pintype "bidirectional"))
      (node (ref "DRIVER3") (pin "15") (pinfunction "GND_15") (pintype "bidirectional"))
      (node (ref "DRIVER4") (pin "15") (pinfunction "GND_15") (pintype "bidirectional"))
      (node (ref "DRIVER5") (pin "15") (pinfunction "GND_15") (pintype "bidirectional"))
      (node (ref "DRIVER6") (pin "15") (pinfunction "GND_15") (pintype "bidirectional"))
      (node (ref "DRIVER7") (pin "15") (pinfunction "GND_15") (pintype "bidirectional"))
      (node (ref "DRIVER8") (pin "15") (pinfunction "GND_15") (pintype "bidirectional"))
      (node (ref "DRIVER9") (pin "15") (pinfunction "GND_15") (pintype "bidirectional"))
      (node (ref "MUX1") (pin "7") (pinfunction "~{ST}_7") (pintype "bidirectional"))
      (node (ref "MUX1") (pin "8") (pinfunction "GND_8") (pintype "bidirectional"))
      (node (ref "MUX2") (pin "7") (pinfunction "~{ST}_7") (pintype "bidirectional"))
      (node (ref "MUX2") (pin "8") (pinfunction "GND_8") (pintype "bidirectional"))
      (node (ref "MUX3") (pin "7") (pinfunction "~{ST}_7") (pintype "bidirectional"))
      (node (ref "MUX3") (pin "8") (pinfunction "GND_8") (pintype "bidirectional"))
      (node (ref "MUX4") (pin "7") (pinfunction "~{ST}_7") (pintype "bidirectional"))
      (node (ref "MUX4") (pin "8") (pinfunction "GND_8") (pintype "bidirectional"))
      (node (ref "MUX4") (pin "9") (pinfunction "C_9") (pintype "bidirectional"))
    )
    (net (code "94") (name "Net-(DMUX1-~{G1})") (class "Default")
      (node (ref "DMUX1") (pin "14") (pinfunction "~{G2}_14") (pintype "bidirectional"))
      (node (ref "DMUX1") (pin "2") (pinfunction "~{G1}_2") (pintype "bidirectional"))
      (node (ref "DMUX4") (pin "9") (pinfunction "~{D0}_9") (pintype "bidirectional"))
    )
    (net (code "95") (name "Net-(DMUX2-~{G1})") (class "Default")
      (node (ref "DMUX2") (pin "14") (pinfunction "~{G2}_14") (pintype "bidirectional"))
      (node (ref "DMUX2") (pin "2") (pinfunction "~{G1}_2") (pintype "bidirectional"))
      (node (ref "DMUX4") (pin "10") (pinfunction "~{D1}_10") (pintype "bidirectional"))
    )
    (net (code "96") (name "Net-(DMUX3-~{G1})") (class "Default")
      (node (ref "DMUX3") (pin "14") (pinfunction "~{G2}_14") (pintype "bidirectional"))
      (node (ref "DMUX3") (pin "2") (pinfunction "~{G1}_2") (pintype "bidirectional"))
      (node (ref "DMUX4") (pin "11") (pinfunction "~{D2}_11") (pintype "bidirectional"))
    )
    (net (code "97") (name "Net-(DRIVER1-C1+)") (class "Default")
      (node (ref "C1") (pin "1") (pinfunction "1_1") (pintype "passive"))
      (node (ref "DRIVER1") (pin "1") (pinfunction "C1+_1") (pintype "bidirectional"))
    )
    (net (code "98") (name "Net-(DRIVER1-C1-)") (class "Default")
      (node (ref "C1") (pin "2") (pinfunction "2_2") (pintype "passive"))
      (node (ref "DRIVER1") (pin "3") (pinfunction "C1-_3") (pintype "bidirectional"))
    )
    (net (code "99") (name "Net-(DRIVER1-C2+)") (class "Default")
      (node (ref "C2") (pin "1") (pinfunction "1_1") (pintype "passive"))
      (node (ref "DRIVER1") (pin "4") (pinfunction "C2+_4") (pintype "bidirectional"))
    )
    (net (code "100") (name "Net-(DRIVER1-C2-)") (class "Default")
      (node (ref "C2") (pin "2") (pinfunction "2_2") (pintype "passive"))
      (node (ref "DRIVER1") (pin "5") (pinfunction "C2-_5") (pintype "bidirectional"))
    )
    (net (code "101") (name "Net-(DRIVER1-VS+)") (class "Default")
      (node (ref "C3") (pin "1") (pinfunction "1_1") (pintype "passive"))
      (node (ref "DRIVER1") (pin "2") (pinfunction "VS+_2") (pintype "bidirectional"))
    )
    (net (code "102") (name "Net-(DRIVER1-VS-)") (class "Default")
      (node (ref "C4") (pin "2") (pinfunction "2_2") (pintype "passive"))
      (node (ref "DRIVER1") (pin "6") (pinfunction "VS-_6") (pintype "bidirectional"))
    )
    (net (code "103") (name "Net-(DRIVER2-C1+)") (class "Default")
      (node (ref "C5") (pin "1") (pinfunction "1_1") (pintype "passive"))
      (node (ref "DRIVER2") (pin "1") (pinfunction "C1+_1") (pintype "bidirectional"))
    )
    (net (code "104") (name "Net-(DRIVER2-C1-)") (class "Default")
      (node (ref "C5") (pin "2") (pinfunction "2_2") (pintype "passive"))
      (node (ref "DRIVER2") (pin "3") (pinfunction "C1-_3") (pintype "bidirectional"))
    )
    (net (code "105") (name "Net-(DRIVER2-C2+)") (class "Default")
      (node (ref "C6") (pin "1") (pinfunction "1_1") (pintype "passive"))
      (node (ref "DRIVER2") (pin "4") (pinfunction "C2+_4") (pintype "bidirectional"))
    )
    (net (code "106") (name "Net-(DRIVER2-C2-)") (class "Default")
      (node (ref "C6") (pin "2") (pinfunction "2_2") (pintype "passive"))
      (node (ref "DRIVER2") (pin "5") (pinfunction "C2-_5") (pintype "bidirectional"))
    )
    (net (code "107") (name "Net-(DRIVER2-VS+)") (class "Default")
      (node (ref "C7") (pin "1") (pinfunction "1_1") (pintype "passive"))
      (node (ref "DRIVER2") (pin "2") (pinfunction "VS+_2") (pintype "bidirectional"))
    )
    (net (code "108") (name "Net-(DRIVER2-VS-)") (class "Default")
      (node (ref "C8") (pin "2") (pinfunction "2_2") (pintype "passive"))
      (node (ref "DRIVER2") (pin "6") (pinfunction "VS-_6") (pintype "bidirectional"))
    )
    (net (code "109") (name "Net-(DRIVER3-C1+)") (class "Default")
      (node (ref "C9") (pin "1") (pinfunction "1_1") (pintype "passive"))
      (node (ref "DRIVER3") (pin "1") (pinfunction "C1+_1") (pintype "bidirectional"))
    )
    (net (code "110") (name "Net-(DRIVER3-C1-)") (class "Default")
      (node (ref "C9") (pin "2") (pinfunction "2_2") (pintype "passive"))
      (node (ref "DRIVER3") (pin "3") (pinfunction "C1-_3") (pintype "bidirectional"))
    )
    (net (code "111") (name "Net-(DRIVER3-C2+)") (class "Default")
      (node (ref "C10") (pin "1") (pinfunction "1_1") (pintype "passive"))
      (node (ref "DRIVER3") (pin "4") (pinfunction "C2+_4") (pintype "bidirectional"))
    )
    (net (code "112") (name "Net-(DRIVER3-C2-)") (class "Default")
      (node (ref "C10") (pin "2") (pinfunction "2_2") (pintype "passive"))
      (node (ref "DRIVER3") (pin "5") (pinfunction "C2-_5") (pintype "bidirectional"))
    )
    (net (code "113") (name "Net-(DRIVER3-VS+)") (class "Default")
      (node (ref "C11") (pin "1") (pinfunction "1_1") (pintype "passive"))
      (node (ref "DRIVER3") (pin "2") (pinfunction "VS+_2") (pintype "bidirectional"))
    )
    (net (code "114") (name "Net-(DRIVER3-VS-)") (class "Default")
      (node (ref "C12") (pin "2") (pinfunction "2_2") (pintype "passive"))
      (node (ref "DRIVER3") (pin "6") (pinfunction "VS-_6") (pintype "bidirectional"))
    )
    (net (code "115") (name "Net-(DRIVER4-C1+)") (class "Default")
      (node (ref "C13") (pin "1") (pinfunction "1_1") (pintype "passive"))
      (node (ref "DRIVER4") (pin "1") (pinfunction "C1+_1") (pintype "bidirectional"))
    )
    (net (code "116") (name "Net-(DRIVER4-C1-)") (class "Default")
      (node (ref "C13") (pin "2") (pinfunction "2_2") (pintype "passive"))
      (node (ref "DRIVER4") (pin "3") (pinfunction "C1-_3") (pintype "bidirectional"))
    )
    (net (code "117") (name "Net-(DRIVER4-C2+)") (class "Default")
      (node (ref "C14") (pin "1") (pinfunction "1_1") (pintype "passive"))
      (node (ref "DRIVER4") (pin "4") (pinfunction "C2+_4") (pintype "bidirectional"))
    )
    (net (code "118") (name "Net-(DRIVER4-C2-)") (class "Default")
      (node (ref "C14") (pin "2") (pinfunction "2_2") (pintype "passive"))
      (node (ref "DRIVER4") (pin "5") (pinfunction "C2-_5") (pintype "bidirectional"))
    )
    (net (code "119") (name "Net-(DRIVER4-VS+)") (class "Default")
      (node (ref "C15") (pin "1") (pinfunction "1_1") (pintype "passive"))
      (node (ref "DRIVER4") (pin "2") (pinfunction "VS+_2") (pintype "bidirectional"))
    )
    (net (code "120") (name "Net-(DRIVER4-VS-)") (class "Default")
      (node (ref "C16") (pin "2") (pinfunction "2_2") (pintype "passive"))
      (node (ref "DRIVER4") (pin "6") (pinfunction "VS-_6") (pintype "bidirectional"))
    )
    (net (code "121") (name "Net-(DRIVER5-C1+)") (class "Default")
      (node (ref "C17") (pin "1") (pinfunction "1_1") (pintype "passive"))
      (node (ref "DRIVER5") (pin "1") (pinfunction "C1+_1") (pintype "bidirectional"))
    )
    (net (code "122") (name "Net-(DRIVER5-C1-)") (class "Default")
      (node (ref "C17") (pin "2") (pinfunction "2_2") (pintype "passive"))
      (node (ref "DRIVER5") (pin "3") (pinfunction "C1-_3") (pintype "bidirectional"))
    )
    (net (code "123") (name "Net-(DRIVER5-C2+)") (class "Default")
      (node (ref "C18") (pin "1") (pinfunction "1_1") (pintype "passive"))
      (node (ref "DRIVER5") (pin "4") (pinfunction "C2+_4") (pintype "bidirectional"))
    )
    (net (code "124") (name "Net-(DRIVER5-C2-)") (class "Default")
      (node (ref "C18") (pin "2") (pinfunction "2_2") (pintype "passive"))
      (node (ref "DRIVER5") (pin "5") (pinfunction "C2-_5") (pintype "bidirectional"))
    )
    (net (code "125") (name "Net-(DRIVER5-VS+)") (class "Default")
      (node (ref "C19") (pin "1") (pinfunction "1_1") (pintype "passive"))
      (node (ref "DRIVER5") (pin "2") (pinfunction "VS+_2") (pintype "bidirectional"))
    )
    (net (code "126") (name "Net-(DRIVER5-VS-)") (class "Default")
      (node (ref "C20") (pin "2") (pinfunction "2_2") (pintype "passive"))
      (node (ref "DRIVER5") (pin "6") (pinfunction "VS-_6") (pintype "bidirectional"))
    )
    (net (code "127") (name "Net-(DRIVER6-C1+)") (class "Default")
      (node (ref "C21") (pin "1") (pinfunction "1_1") (pintype "passive"))
      (node (ref "DRIVER6") (pin "1") (pinfunction "C1+_1") (pintype "bidirectional"))
    )
    (net (code "128") (name "Net-(DRIVER6-C1-)") (class "Default")
      (node (ref "C21") (pin "2") (pinfunction "2_2") (pintype "passive"))
      (node (ref "DRIVER6") (pin "3") (pinfunction "C1-_3") (pintype "bidirectional"))
    )
    (net (code "129") (name "Net-(DRIVER6-C2+)") (class "Default")
      (node (ref "C22") (pin "1") (pinfunction "1_1") (pintype "passive"))
      (node (ref "DRIVER6") (pin "4") (pinfunction "C2+_4") (pintype "bidirectional"))
    )
    (net (code "130") (name "Net-(DRIVER6-C2-)") (class "Default")
      (node (ref "C22") (pin "2") (pinfunction "2_2") (pintype "passive"))
      (node (ref "DRIVER6") (pin "5") (pinfunction "C2-_5") (pintype "bidirectional"))
    )
    (net (code "131") (name "Net-(DRIVER6-VS+)") (class "Default")
      (node (ref "C23") (pin "1") (pinfunction "1_1") (pintype "passive"))
      (node (ref "DRIVER6") (pin "2") (pinfunction "VS+_2") (pintype "bidirectional"))
    )
    (net (code "132") (name "Net-(DRIVER6-VS-)") (class "Default")
      (node (ref "C24") (pin "2") (pinfunction "2_2") (pintype "passive"))
      (node (ref "DRIVER6") (pin "6") (pinfunction "VS-_6") (pintype "bidirectional"))
    )
    (net (code "133") (name "Net-(DRIVER7-C1+)") (class "Default")
      (node (ref "C25") (pin "1") (pinfunction "1_1") (pintype "passive"))
      (node (ref "DRIVER7") (pin "1") (pinfunction "C1+_1") (pintype "bidirectional"))
    )
    (net (code "134") (name "Net-(DRIVER7-C1-)") (class "Default")
      (node (ref "C25") (pin "2") (pinfunction "2_2") (pintype "passive"))
      (node (ref "DRIVER7") (pin "3") (pinfunction "C1-_3") (pintype "bidirectional"))
    )
    (net (code "135") (name "Net-(DRIVER7-C2+)") (class "Default")
      (node (ref "C26") (pin "1") (pinfunction "1_1") (pintype "passive"))
      (node (ref "DRIVER7") (pin "4") (pinfunction "C2+_4") (pintype "bidirectional"))
    )
    (net (code "136") (name "Net-(DRIVER7-C2-)") (class "Default")
      (node (ref "C26") (pin "2") (pinfunction "2_2") (pintype "passive"))
      (node (ref "DRIVER7") (pin "5") (pinfunction "C2-_5") (pintype "bidirectional"))
    )
    (net (code "137") (name "Net-(DRIVER7-VS+)") (class "Default")
      (node (ref "C27") (pin "1") (pinfunction "1_1") (pintype "passive"))
      (node (ref "DRIVER7") (pin "2") (pinfunction "VS+_2") (pintype "bidirectional"))
    )
    (net (code "138") (name "Net-(DRIVER7-VS-)") (class "Default")
      (node (ref "C28") (pin "2") (pinfunction "2_2") (pintype "passive"))
      (node (ref "DRIVER7") (pin "6") (pinfunction "VS-_6") (pintype "bidirectional"))
    )
    (net (code "139") (name "Net-(DRIVER8-C1+)") (class "Default")
      (node (ref "C29") (pin "1") (pinfunction "1_1") (pintype "passive"))
      (node (ref "DRIVER8") (pin "1") (pinfunction "C1+_1") (pintype "bidirectional"))
    )
    (net (code "140") (name "Net-(DRIVER8-C1-)") (class "Default")
      (node (ref "C29") (pin "2") (pinfunction "2_2") (pintype "passive"))
      (node (ref "DRIVER8") (pin "3") (pinfunction "C1-_3") (pintype "bidirectional"))
    )
    (net (code "141") (name "Net-(DRIVER8-C2+)") (class "Default")
      (node (ref "C30") (pin "1") (pinfunction "1_1") (pintype "passive"))
      (node (ref "DRIVER8") (pin "4") (pinfunction "C2+_4") (pintype "bidirectional"))
    )
    (net (code "142") (name "Net-(DRIVER8-C2-)") (class "Default")
      (node (ref "C30") (pin "2") (pinfunction "2_2") (pintype "passive"))
      (node (ref "DRIVER8") (pin "5") (pinfunction "C2-_5") (pintype "bidirectional"))
    )
    (net (code "143") (name "Net-(DRIVER8-VS+)") (class "Default")
      (node (ref "C31") (pin "1") (pinfunction "1_1") (pintype "passive"))
      (node (ref "DRIVER8") (pin "2") (pinfunction "VS+_2") (pintype "bidirectional"))
    )
    (net (code "144") (name "Net-(DRIVER8-VS-)") (class "Default")
      (node (ref "C32") (pin "2") (pinfunction "2_2") (pintype "passive"))
      (node (ref "DRIVER8") (pin "6") (pinfunction "VS-_6") (pintype "bidirectional"))
    )
    (net (code "145") (name "Net-(DRIVER9-C1+)") (class "Default")
      (node (ref "C33") (pin "1") (pinfunction "1_1") (pintype "passive"))
      (node (ref "DRIVER9") (pin "1") (pinfunction "C1+_1") (pintype "bidirectional"))
    )
    (net (code "146") (name "Net-(DRIVER9-C1-)") (class "Default")
      (node (ref "C33") (pin "2") (pinfunction "2_2") (pintype "passive"))
      (node (ref "DRIVER9") (pin "3") (pinfunction "C1-_3") (pintype "bidirectional"))
    )
    (net (code "147") (name "Net-(DRIVER9-C2+)") (class "Default")
      (node (ref "C34") (pin "1") (pinfunction "1_1") (pintype "passive"))
      (node (ref "DRIVER9") (pin "4") (pinfunction "C2+_4") (pintype "bidirectional"))
    )
    (net (code "148") (name "Net-(DRIVER9-C2-)") (class "Default")
      (node (ref "C34") (pin "2") (pinfunction "2_2") (pintype "passive"))
      (node (ref "DRIVER9") (pin "5") (pinfunction "C2-_5") (pintype "bidirectional"))
    )
    (net (code "149") (name "Net-(DRIVER9-VS+)") (class "Default")
      (node (ref "C35") (pin "1") (pinfunction "1_1") (pintype "passive"))
      (node (ref "DRIVER9") (pin "2") (pinfunction "VS+_2") (pintype "bidirectional"))
    )
    (net (code "150") (name "Net-(DRIVER9-VS-)") (class "Default")
      (node (ref "C36") (pin "2") (pinfunction "2_2") (pintype "passive"))
      (node (ref "DRIVER9") (pin "6") (pinfunction "VS-_6") (pintype "bidirectional"))
    )
    (net (code "151") (name "Net-(DRIVER10-C1+)") (class "Default")
      (node (ref "C37") (pin "1") (pinfunction "1_1") (pintype "passive"))
      (node (ref "DRIVER10") (pin "1") (pinfunction "C1+_1") (pintype "bidirectional"))
    )
    (net (code "152") (name "Net-(DRIVER10-C1-)") (class "Default")
      (node (ref "C37") (pin "2") (pinfunction "2_2") (pintype "passive"))
      (node (ref "DRIVER10") (pin "3") (pinfunction "C1-_3") (pintype "bidirectional"))
    )
    (net (code "153") (name "Net-(DRIVER10-C2+)") (class "Default")
      (node (ref "C38") (pin "1") (pinfunction "1_1") (pintype "passive"))
      (node (ref "DRIVER10") (pin "4") (pinfunction "C2+_4") (pintype "bidirectional"))
    )
    (net (code "154") (name "Net-(DRIVER10-C2-)") (class "Default")
      (node (ref "C38") (pin "2") (pinfunction "2_2") (pintype "passive"))
      (node (ref "DRIVER10") (pin "5") (pinfunction "C2-_5") (pintype "bidirectional"))
    )
    (net (code "155") (name "Net-(DRIVER10-VS+)") (class "Default")
      (node (ref "C39") (pin "1") (pinfunction "1_1") (pintype "passive"))
      (node (ref "DRIVER10") (pin "2") (pinfunction "VS+_2") (pintype "bidirectional"))
    )
    (net (code "156") (name "Net-(DRIVER10-VS-)") (class "Default")
      (node (ref "C40") (pin "2") (pinfunction "2_2") (pintype "passive"))
      (node (ref "DRIVER10") (pin "6") (pinfunction "VS-_6") (pintype "bidirectional"))
    )
    (net (code "157") (name "Net-(DRIVER11-C1+)") (class "Default")
      (node (ref "C41") (pin "1") (pinfunction "1_1") (pintype "passive"))
      (node (ref "DRIVER11") (pin "1") (pinfunction "C1+_1") (pintype "bidirectional"))
    )
    (net (code "158") (name "Net-(DRIVER11-C1-)") (class "Default")
      (node (ref "C41") (pin "2") (pinfunction "2_2") (pintype "passive"))
      (node (ref "DRIVER11") (pin "3") (pinfunction "C1-_3") (pintype "bidirectional"))
    )
    (net (code "159") (name "Net-(DRIVER11-C2+)") (class "Default")
      (node (ref "C42") (pin "1") (pinfunction "1_1") (pintype "passive"))
      (node (ref "DRIVER11") (pin "4") (pinfunction "C2+_4") (pintype "bidirectional"))
    )
    (net (code "160") (name "Net-(DRIVER11-C2-)") (class "Default")
      (node (ref "C42") (pin "2") (pinfunction "2_2") (pintype "passive"))
      (node (ref "DRIVER11") (pin "5") (pinfunction "C2-_5") (pintype "bidirectional"))
    )
    (net (code "161") (name "Net-(DRIVER11-VS+)") (class "Default")
      (node (ref "C43") (pin "1") (pinfunction "1_1") (pintype "passive"))
      (node (ref "DRIVER11") (pin "2") (pinfunction "VS+_2") (pintype "bidirectional"))
    )
    (net (code "162") (name "Net-(DRIVER11-VS-)") (class "Default")
      (node (ref "C44") (pin "2") (pinfunction "2_2") (pintype "passive"))
      (node (ref "DRIVER11") (pin "6") (pinfunction "VS-_6") (pintype "bidirectional"))
    )
    (net (code "163") (name "Net-(DRIVER12-C1+)") (class "Default")
      (node (ref "C45") (pin "1") (pinfunction "1_1") (pintype "passive"))
      (node (ref "DRIVER12") (pin "1") (pinfunction "C1+_1") (pintype "bidirectional"))
    )
    (net (code "164") (name "Net-(DRIVER12-C1-)") (class "Default")
      (node (ref "C45") (pin "2") (pinfunction "2_2") (pintype "passive"))
      (node (ref "DRIVER12") (pin "3") (pinfunction "C1-_3") (pintype "bidirectional"))
    )
    (net (code "165") (name "Net-(DRIVER12-C2+)") (class "Default")
      (node (ref "C46") (pin "1") (pinfunction "1_1") (pintype "passive"))
      (node (ref "DRIVER12") (pin "4") (pinfunction "C2+_4") (pintype "bidirectional"))
    )
    (net (code "166") (name "Net-(DRIVER12-C2-)") (class "Default")
      (node (ref "C46") (pin "2") (pinfunction "2_2") (pintype "passive"))
      (node (ref "DRIVER12") (pin "5") (pinfunction "C2-_5") (pintype "bidirectional"))
    )
    (net (code "167") (name "Net-(DRIVER12-VS+)") (class "Default")
      (node (ref "C47") (pin "1") (pinfunction "1_1") (pintype "passive"))
      (node (ref "DRIVER12") (pin "2") (pinfunction "VS+_2") (pintype "bidirectional"))
    )
    (net (code "168") (name "Net-(DRIVER12-VS-)") (class "Default")
      (node (ref "C48") (pin "2") (pinfunction "2_2") (pintype "passive"))
      (node (ref "DRIVER12") (pin "6") (pinfunction "VS-_6") (pintype "bidirectional"))
    )
    (net (code "169") (name "Net-(MUX1-Y)") (class "Default")
      (node (ref "MUX1") (pin "5") (pinfunction "Y_5") (pintype "bidirectional"))
      (node (ref "MUX4") (pin "4") (pinfunction "D0_4") (pintype "bidirectional"))
    )
    (net (code "170") (name "Net-(MUX2-Y)") (class "Default")
      (node (ref "MUX2") (pin "5") (pinfunction "Y_5") (pintype "bidirectional"))
      (node (ref "MUX4") (pin "3") (pinfunction "D1_3") (pintype "bidirectional"))
    )
    (net (code "171") (name "Net-(MUX3-Y)") (class "Default")
      (node (ref "MUX3") (pin "5") (pinfunction "Y_5") (pintype "bidirectional"))
      (node (ref "MUX4") (pin "2") (pinfunction "D2_2") (pintype "bidirectional"))
    )
    (net (code "172") (name "SEL0") (class "Default")
      (node (ref "DMUX1") (pin "13") (pinfunction "A_13") (pintype "bidirectional"))
      (node (ref "DMUX2") (pin "13") (pinfunction "A_13") (pintype "bidirectional"))
      (node (ref "DMUX3") (pin "13") (pinfunction "A_13") (pintype "bidirectional"))
      (node (ref "MUX1") (pin "11") (pinfunction "A_11") (pintype "bidirectional"))
      (node (ref "MUX2") (pin "11") (pinfunction "A_11") (pintype "bidirectional"))
      (node (ref "MUX3") (pin "11") (pinfunction "A_11") (pintype "bidirectional"))
    )
    (net (code "173") (name "SEL1") (class "Default")
      (node (ref "DMUX1") (pin "3") (pinfunction "B_3") (pintype "bidirectional"))
      (node (ref "DMUX2") (pin "3") (pinfunction "B_3") (pintype "bidirectional"))
      (node (ref "DMUX3") (pin "3") (pinfunction "B_3") (pintype "bidirectional"))
      (node (ref "MUX1") (pin "10") (pinfunction "B_10") (pintype "bidirectional"))
      (node (ref "MUX2") (pin "10") (pinfunction "B_10") (pintype "bidirectional"))
      (node (ref "MUX3") (pin "10") (pinfunction "B_10") (pintype "bidirectional"))
    )
    (net (code "174") (name "SEL2") (class "Default")
      (node (ref "DMUX1") (pin "1") (pinfunction "C1_1") (pintype "bidirectional"))
      (node (ref "DMUX1") (pin "15") (pinfunction "C2_15") (pintype "bidirectional"))
      (node (ref "DMUX2") (pin "1") (pinfunction "C1_1") (pintype "bidirectional"))
      (node (ref "DMUX2") (pin "15") (pinfunction "C2_15") (pintype "bidirectional"))
      (node (ref "DMUX3") (pin "1") (pinfunction "C1_1") (pintype "bidirectional"))
      (node (ref "DMUX3") (pin "15") (pinfunction "C2_15") (pintype "bidirectional"))
      (node (ref "MUX1") (pin "9") (pinfunction "C_9") (pintype "bidirectional"))
      (node (ref "MUX2") (pin "9") (pinfunction "C_9") (pintype "bidirectional"))
      (node (ref "MUX3") (pin "9") (pinfunction "C_9") (pintype "bidirectional"))
    )
    (net (code "175") (name "SEL3") (class "Default")
      (node (ref "DMUX4") (pin "13") (pinfunction "A_13") (pintype "bidirectional"))
      (node (ref "MUX4") (pin "11") (pinfunction "A_11") (pintype "bidirectional"))
    )
    (net (code "176") (name "SEL4") (class "Default")
      (node (ref "DMUX4") (pin "3") (pinfunction "B_3") (pintype "bidirectional"))
      (node (ref "MUX4") (pin "10") (pinfunction "B_10") (pintype "bidirectional"))
    )
    (net (code "177") (name "VCC") (class "Default")
      (node (ref "DMUX1") (pin "16") (pinfunction "VCC_16") (pintype "bidirectional"))
      (node (ref "DMUX2") (pin "16") (pinfunction "VCC_16") (pintype "bidirectional"))
      (node (ref "DMUX3") (pin "16") (pinfunction "VCC_16") (pintype "bidirectional"))
      (node (ref "DMUX4") (pin "16") (pinfunction "VCC_16") (pintype "bidirectional"))
      (node (ref "DRIVER1") (pin "16") (pinfunction "VCC_16") (pintype "bidirectional"))
      (node (ref "DRIVER10") (pin "16") (pinfunction "VCC_16") (pintype "bidirectional"))
      (node (ref "DRIVER11") (pin "16") (pinfunction "VCC_16") (pintype "bidirectional"))
      (node (ref "DRIVER12") (pin "16") (pinfunction "VCC_16") (pintype "bidirectional"))
      (node (ref "DRIVER2") (pin "16") (pinfunction "VCC_16") (pintype "bidirectional"))
      (node (ref "DRIVER3") (pin "16") (pinfunction "VCC_16") (pintype "bidirectional"))
      (node (ref "DRIVER4") (pin "16") (pinfunction "VCC_16") (pintype "bidirectional"))
      (node (ref "DRIVER5") (pin "16") (pinfunction "VCC_16") (pintype "bidirectional"))
      (node (ref "DRIVER6") (pin "16") (pinfunction "VCC_16") (pintype "bidirectional"))
      (node (ref "DRIVER7") (pin "16") (pinfunction "VCC_16") (pintype "bidirectional"))
      (node (ref "DRIVER8") (pin "16") (pinfunction "VCC_16") (pintype "bidirectional"))
      (node (ref "DRIVER9") (pin "16") (pinfunction "VCC_16") (pintype "bidirectional"))
      (node (ref "MUX1") (pin "16") (pinfunction "VCC_16") (pintype "bidirectional"))
      (node (ref "MUX2") (pin "16") (pinfunction "VCC_16") (pintype "bidirectional"))
      (node (ref "MUX3") (pin "16") (pinfunction "VCC_16") (pintype "bidirectional"))
      (node (ref "MUX4") (pin "16") (pinfunction "VCC_16") (pintype "bidirectional"))
    )
    (net (code "178") (name "unconnected-(DMUX3-~{D6}-Pad5)") (class "Default")
      (node (ref "DMUX3") (pin "5") (pinfunction "~{D6}_5") (pintype "bidirectional"))
    )
    (net (code "179") (name "unconnected-(DMUX3-~{D7}-Pad4)") (class "Default")
      (node (ref "DMUX3") (pin "4") (pinfunction "~{D7}_4") (pintype "bidirectional"))
    )
    (net (code "180") (name "unconnected-(DMUX4-~{D3}-Pad12)") (class "Default")
      (node (ref "DMUX4") (pin "12") (pinfunction "~{D3}_12") (pintype "bidirectional"))
    )
    (net (code "181") (name "unconnected-(DMUX4-~{D4}-Pad7)") (class "Default")
      (node (ref "DMUX4") (pin "7") (pinfunction "~{D4}_7") (pintype "bidirectional"))
    )
    (net (code "182") (name "unconnected-(DMUX4-~{D5}-Pad6)") (class "Default")
      (node (ref "DMUX4") (pin "6") (pinfunction "~{D5}_6") (pintype "bidirectional"))
    )
    (net (code "183") (name "unconnected-(DMUX4-~{D6}-Pad5)") (class "Default")
      (node (ref "DMUX4") (pin "5") (pinfunction "~{D6}_5") (pintype "bidirectional"))
    )
    (net (code "184") (name "unconnected-(DMUX4-~{D7}-Pad4)") (class "Default")
      (node (ref "DMUX4") (pin "4") (pinfunction "~{D7}_4") (pintype "bidirectional"))
    )
    (net (code "185") (name "unconnected-(DRIVER12-RS232_IN2-Pad8)") (class "Default")
      (node (ref "DRIVER12") (pin "8") (pinfunction "RS232_IN2_8") (pintype "bidirectional"))
    )
    (net (code "186") (name "unconnected-(DRIVER12-RS232_OUT2-Pad7)") (class "Default")
      (node (ref "DRIVER12") (pin "7") (pinfunction "RS232_OUT2_7") (pintype "bidirectional"))
    )
    (net (code "187") (name "unconnected-(DRIVER12-TTL_IN2-Pad10)") (class "Default")
      (node (ref "DRIVER12") (pin "10") (pinfunction "TTL_IN2_10") (pintype "bidirectional"))
    )
    (net (code "188") (name "unconnected-(DRIVER12-TTL_OUT2-Pad9)") (class "Default")
      (node (ref "DRIVER12") (pin "9") (pinfunction "TTL_OUT2_9") (pintype "bidirectional"))
    )
    (net (code "189") (name "unconnected-(MUX1-W-Pad6)") (class "Default")
      (node (ref "MUX1") (pin "6") (pinfunction "W_6") (pintype "bidirectional"))
    )
    (net (code "190") (name "unconnected-(MUX2-W-Pad6)") (class "Default")
      (node (ref "MUX2") (pin "6") (pinfunction "W_6") (pintype "bidirectional"))
    )
    (net (code "191") (name "unconnected-(MUX3-D6-Pad13)") (class "Default")
      (node (ref "MUX3") (pin "13") (pinfunction "D6_13") (pintype "bidirectional"))
    )
    (net (code "192") (name "unconnected-(MUX3-D7-Pad12)") (class "Default")
      (node (ref "MUX3") (pin "12") (pinfunction "D7_12") (pintype "bidirectional"))
    )
    (net (code "193") (name "unconnected-(MUX3-W-Pad6)") (class "Default")
      (node (ref "MUX3") (pin "6") (pinfunction "W_6") (pintype "bidirectional"))
    )
    (net (code "194") (name "unconnected-(MUX4-D3-Pad1)") (class "Default")
      (node (ref "MUX4") (pin "1") (pinfunction "D3_1") (pintype "bidirectional"))
    )
    (net (code "195") (name "unconnected-(MUX4-D4-Pad15)") (class "Default")
      (node (ref "MUX4") (pin "15") (pinfunction "D4_15") (pintype "bidirectional"))
    )
    (net (code "196") (name "unconnected-(MUX4-D5-Pad14)") (class "Default")
      (node (ref "MUX4") (pin "14") (pinfunction "D5_14") (pintype "bidirectional"))
    )
    (net (code "197") (name "unconnected-(MUX4-D6-Pad13)") (class "Default")
      (node (ref "MUX4") (pin "13") (pinfunction "D6_13") (pintype "bidirectional"))
    )
    (net (code "198") (name "unconnected-(MUX4-D7-Pad12)") (class "Default")
      (node (ref "MUX4") (pin "12") (pinfunction "D7_12") (pintype "bidirectional"))
    )
    (net (code "199") (name "unconnected-(MUX4-W-Pad6)") (class "Default")
      (node (ref "MUX4") (pin "6") (pinfunction "W_6") (pintype "bidirectional"))
    )
  )
)
